# LEDDriver.net
KiCad netlist of a schematic drawn in EAGLE
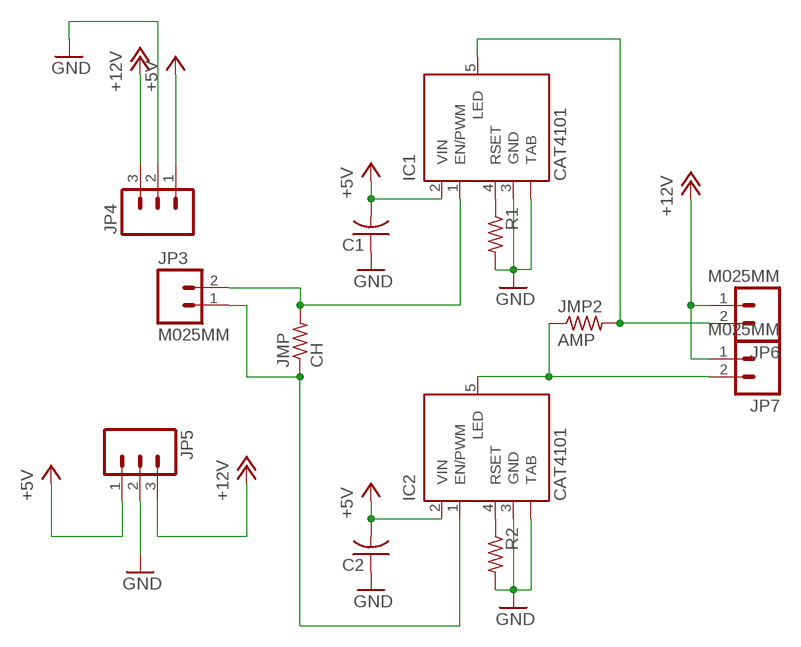
[diagram p0: schematic, sheet 1]

(export (version "E")
  (design (tool "Eeschema 10.0.6"))
  (components
    (comp (ref "C1")
      (value "C-USC1206")
      (footprint "eagle-import:C1206")
      (libsource (lib "eagle-import") (part "C-USC1206"))
    )
    (comp (ref "C2")
      (value "C-USC1206")
      (footprint "eagle-import:C1206")
      (libsource (lib "eagle-import") (part "C-USC1206"))
    )
    (comp (ref "IC1")
      (value "CAT4101")
      (footprint "eagle-import:TO263_5")
      (fields (field (name "MPN") "CAT4101TV-T75"))
      (libsource (lib "eagle-import") (part "CAT4101"))
    )
    (comp (ref "IC2")
      (value "CAT4101")
      (footprint "eagle-import:TO263_5")
      (fields (field (name "MPN") "CAT4101TV-T75"))
      (libsource (lib "eagle-import") (part "CAT4101"))
    )
    (comp (ref "JMP")
      (value "CH")
      (footprint "eagle-import:R1206")
      (libsource (lib "eagle-import") (part "R-US_R1206"))
    )
    (comp (ref "JMP2")
      (value "AMP")
      (footprint "eagle-import:R1206")
      (libsource (lib "eagle-import") (part "R-US_R1206"))
    )
    (comp (ref "JP3")
      (value "M025MM")
      (footprint "eagle-import:SCREWTERMINAL-5MM-2")
      (libsource (lib "eagle-import") (part "M025MM"))
    )
    (comp (ref "JP4")
      (value "M03-SCREW-5MM")
      (footprint "eagle-import:SCREWTERMINAL-5MM-3")
      (libsource (lib "eagle-import") (part "M03-SCREW-5MM"))
    )
    (comp (ref "JP5")
      (value "M03-SCREW-5MM")
      (footprint "eagle-import:SCREWTERMINAL-5MM-3")
      (libsource (lib "eagle-import") (part "M03-SCREW-5MM"))
    )
    (comp (ref "JP6")
      (value "M025MM")
      (footprint "eagle-import:SCREWTERMINAL-5MM-2")
      (libsource (lib "eagle-import") (part "M025MM"))
    )
    (comp (ref "JP7")
      (value "M025MM")
      (footprint "eagle-import:SCREWTERMINAL-5MM-2")
      (libsource (lib "eagle-import") (part "M025MM"))
    )
    (comp (ref "R1")
      (value "R-US_R1206")
      (footprint "eagle-import:R1206")
      (libsource (lib "eagle-import") (part "R-US_R1206"))
    )
    (comp (ref "R2")
      (value "R-US_R1206")
      (footprint "eagle-import:R1206")
      (libsource (lib "eagle-import") (part "R-US_R1206"))
    )
  )
  (nets
    (net (code "1") (name "+5V") (class "Default")
      (node (ref "C1") (pin "2") (pinfunction "2_2") (pintype "passive"))
      (node (ref "C2") (pin "2") (pinfunction "2_2") (pintype "passive"))
      (node (ref "IC1") (pin "2") (pinfunction "VIN_2") (pintype "input"))
      (node (ref "IC2") (pin "2") (pinfunction "VIN_2") (pintype "input"))
      (node (ref "JP4") (pin "1") (pinfunction "1_1") (pintype "passive"))
      (node (ref "JP5") (pin "1") (pinfunction "1_1") (pintype "passive"))
    )
    (net (code "2") (name "+12V") (class "Default")
      (node (ref "JP4") (pin "3") (pinfunction "3_3") (pintype "passive"))
      (node (ref "JP5") (pin "3") (pinfunction "3_3") (pintype "passive"))
      (node (ref "JP6") (pin "1") (pinfunction "1_1") (pintype "passive"))
      (node (ref "JP7") (pin "1") (pinfunction "1_1") (pintype "passive"))
    )
    (net (code "3") (name "GND") (class "Default")
      (node (ref "C1") (pin "1") (pinfunction "1_1") (pintype "passive"))
      (node (ref "C2") (pin "1") (pinfunction "1_1") (pintype "passive"))
      (node (ref "IC1") (pin "3") (pinfunction "GND_3") (pintype "power_in"))
      (node (ref "IC1") (pin "TAB") (pinfunction "TAB_TAB") (pintype "passive"))
      (node (ref "IC2") (pin "3") (pinfunction "GND_3") (pintype "power_in"))
      (node (ref "IC2") (pin "TAB") (pinfunction "TAB_TAB") (pintype "passive"))
      (node (ref "JP4") (pin "2") (pinfunction "2_2") (pintype "passive"))
      (node (ref "JP5") (pin "2") (pinfunction "2_2") (pintype "passive"))
      (node (ref "R1") (pin "2") (pinfunction "2_2") (pintype "passive"))
      (node (ref "R2") (pin "2") (pinfunction "2_2") (pintype "passive"))
    )
    (net (code "4") (name "Net-(IC1-EN{slash}PWM)") (class "Default")
      (node (ref "IC1") (pin "1") (pinfunction "EN/PWM_1") (pintype "input"))
      (node (ref "JMP") (pin "2") (pinfunction "2_2") (pintype "passive"))
      (node (ref "JP3") (pin "2") (pinfunction "2_2") (pintype "passive"))
    )
    (net (code "5") (name "Net-(IC1-LED)") (class "Default")
      (node (ref "IC1") (pin "5") (pinfunction "LED_5") (pintype "power_in"))
      (node (ref "JMP2") (pin "2") (pinfunction "2_2") (pintype "passive"))
      (node (ref "JP6") (pin "2") (pinfunction "2_2") (pintype "passive"))
    )
    (net (code "6") (name "Net-(IC1-RSET)") (class "Default")
      (node (ref "IC1") (pin "4") (pinfunction "RSET_4") (pintype "input"))
      (node (ref "R1") (pin "1") (pinfunction "1_1") (pintype "passive"))
    )
    (net (code "7") (name "Net-(IC2-EN{slash}PWM)") (class "Default")
      (node (ref "IC2") (pin "1") (pinfunction "EN/PWM_1") (pintype "input"))
      (node (ref "JMP") (pin "1") (pinfunction "1_1") (pintype "passive"))
      (node (ref "JP3") (pin "1") (pinfunction "1_1") (pintype "passive"))
    )
    (net (code "8") (name "Net-(IC2-LED)") (class "Default")
      (node (ref "IC2") (pin "5") (pinfunction "LED_5") (pintype "power_in"))
      (node (ref "JMP2") (pin "1") (pinfunction "1_1") (pintype "passive"))
      (node (ref "JP7") (pin "2") (pinfunction "2_2") (pintype "passive"))
    )
    (net (code "9") (name "Net-(IC2-RSET)") (class "Default")
      (node (ref "IC2") (pin "4") (pinfunction "RSET_4") (pintype "input"))
      (node (ref "R2") (pin "1") (pinfunction "1_1") (pintype "passive"))
    )
  )
)
